# demo.net
KiCad netlist of a schematic drawn in EasyEDA
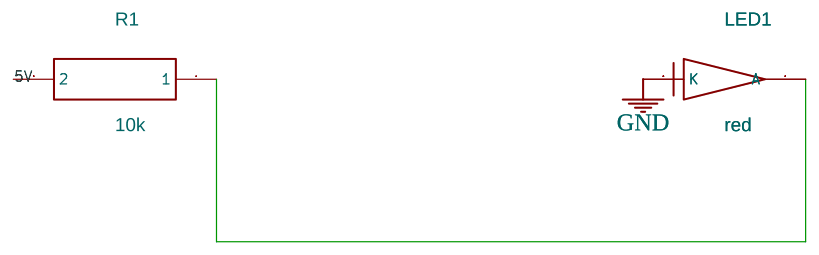
[diagram p0: schematic sheet]

(export (version "E")
  (design (tool "Eeschema 10.0.6"))
  (components
    (comp (ref "LED1") (value "red") (libsource (lib "") (part "led")))
    (comp (ref "R1") (value "10k") (libsource (lib "") (part "resistor")))
  )
  (nets
    (net (code "1") (name "/5V") (class "Default")
      (node (ref "R1") (pin "2") (pinfunction "2_2") (pintype "unspecified"))
    )
    (net (code "2") (name "GND") (class "Default")
      (node (ref "LED1") (pin "2") (pinfunction "K_2") (pintype "unspecified"))
    )
    (net (code "3") (name "Net-(LED1-A)") (class "Default")
      (node (ref "LED1") (pin "1") (pinfunction "A_1") (pintype "unspecified"))
      (node (ref "R1") (pin "1") (pinfunction "1_1") (pintype "unspecified"))
    )
  )
)
